# mcu-osc.net
KiCad netlist of a schematic drawn in Altium Designer
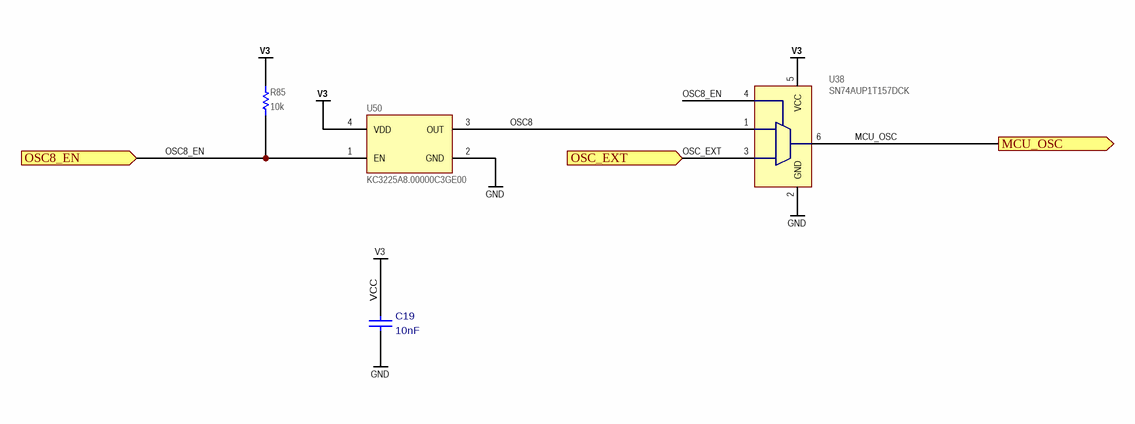
[diagram p0: mcu-osc.SchDoc]

(export (version "E")
  (design (tool "Eeschema 10.0.6"))
  (components
    (comp (ref "C19")
      (value "10nF")
      (footprint "CAPC100X50X55L25N")
      (description "Ceramic Capacitor 10nF ±10% 50V X7R 0402")
      (fields (field (name "MANUFACTURER") "Murata") (field (name "TOLERANCE") "±10%"))
      (libsource (lib "capacitors") (part "CAP"))
    )
    (comp (ref "R85")
      (value "10k")
      (footprint "RESC1005X40N")
      (description "Thick Film Resistor 10k ±1% 0.1W 50V 0402")
      (fields (field (name "MANUFACTURER") "Panasonic") (field (name "TOLERANCE") "±1%"))
      (libsource (lib "generic") (part "RES"))
    )
    (comp (ref "U38")
      (value "SN74AUP1T157DCK")
      (footprint "generic:SOT363")
      (description "Buffer Multiplexer")
      (fields (field (name "MANUFACTURER") "Texas Instruments"))
      (libsource (lib "ti") (part "SN74AUP1T157DCK"))
    )
    (comp (ref "U50")
      (value "KC3225A8.00000C3GE00")
      (footprint "OSCCC320X250X80L75X100N")
      (description "Oscillator 8Mhz")
      (fields (field (name "MANUFACTURER") "Kyocera"))
      (libsource (lib "MCD_TOOLS") (part "OSC_25M_NZ2520SB"))
    )
  )
  (nets
    (net (code "1") (name "/MCU_OSC") (class "Default")
      (node (ref "U38") (pin "6") (pinfunction "Y_6") (pintype "passive"))
    )
    (net (code "2") (name "/OSC8") (class "Default")
      (node (ref "U38") (pin "1") (pinfunction "A_1") (pintype "passive"))
      (node (ref "U50") (pin "3") (pinfunction "OUT_3") (pintype "passive"))
    )
    (net (code "3") (name "/OSC8_EN") (class "Default")
      (node (ref "R85") (pin "1") (pinfunction "1_1") (pintype "passive"))
      (node (ref "U38") (pin "4") (pinfunction "C_4") (pintype "passive"))
      (node (ref "U50") (pin "1") (pinfunction "EN_1") (pintype "passive"))
    )
    (net (code "4") (name "/OSC_EXT") (class "Default")
      (node (ref "U38") (pin "3") (pinfunction "B_3") (pintype "passive"))
    )
    (net (code "5") (name "GND") (class "Default")
      (node (ref "C19") (pin "2") (pinfunction "2_2") (pintype "passive"))
      (node (ref "U38") (pin "2") (pinfunction "GND_2") (pintype "passive"))
      (node (ref "U50") (pin "2") (pinfunction "GND_2") (pintype "passive"))
    )
    (net (code "6") (name "V3") (class "Default")
      (node (ref "C19") (pin "1") (pinfunction "1_1") (pintype "passive"))
      (node (ref "R85") (pin "2") (pinfunction "2_2") (pintype "passive"))
      (node (ref "U38") (pin "5") (pinfunction "VCC_5") (pintype "passive"))
      (node (ref "U50") (pin "4") (pinfunction "VDD_4") (pintype "passive"))
    )
  )
)
